# caps.net
KiCad netlist of a schematic drawn in EAGLE
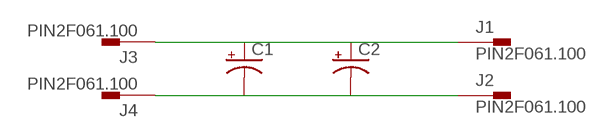
[diagram p0: schematic, sheet 1]

(export (version "E")
  (design (tool "Eeschema 10.0.6"))
  (components
    (comp (ref "C1")
      (value "CPOL-USE10-35")
      (footprint "eagle-import:EB35D")
      (libsource (lib "eagle-import") (part "CPOL-USE10-35"))
    )
    (comp (ref "C2")
      (value "CPOL-USE10-35")
      (footprint "eagle-import:EB35D")
      (libsource (lib "eagle-import") (part "CPOL-USE10-35"))
    )
    (comp (ref "J1")
      (value "PIN2F061.100")
      (footprint "eagle-import:F061.100")
      (libsource (lib "eagle-import") (part "PIN2F061.100"))
    )
    (comp (ref "J2")
      (value "PIN2F061.100")
      (footprint "eagle-import:F061.100")
      (libsource (lib "eagle-import") (part "PIN2F061.100"))
    )
    (comp (ref "J3")
      (value "PIN2F061.100")
      (footprint "eagle-import:F061.100")
      (libsource (lib "eagle-import") (part "PIN2F061.100"))
    )
    (comp (ref "J4")
      (value "PIN2F061.100")
      (footprint "eagle-import:F061.100")
      (libsource (lib "eagle-import") (part "PIN2F061.100"))
    )
  )
  (nets
    (net (code "1") (name "Net-(C1-Pad+)") (class "Default")
      (node (ref "C1") (pin "+") (pinfunction "+_+") (pintype "passive"))
      (node (ref "C2") (pin "+") (pinfunction "+_+") (pintype "passive"))
      (node (ref "J1") (pin "A1") (pinfunction "1_A1") (pintype "passive"))
      (node (ref "J1") (pin "A2") (pinfunction "1_A2") (pintype "passive"))
      (node (ref "J3") (pin "A1") (pinfunction "1_A1") (pintype "passive"))
      (node (ref "J3") (pin "A2") (pinfunction "1_A2") (pintype "passive"))
    )
    (net (code "2") (name "Net-(C1-Pad-)") (class "Default")
      (node (ref "C1") (pin "-") (pinfunction "-_-") (pintype "passive"))
      (node (ref "C2") (pin "-") (pinfunction "-_-") (pintype "passive"))
      (node (ref "J2") (pin "A1") (pinfunction "1_A1") (pintype "passive"))
      (node (ref "J2") (pin "A2") (pinfunction "1_A2") (pintype "passive"))
      (node (ref "J4") (pin "A1") (pinfunction "1_A1") (pintype "passive"))
      (node (ref "J4") (pin "A2") (pinfunction "1_A2") (pintype "passive"))
    )
  )
)
